# GAlarm-board.net
KiCad netlist of a schematic drawn in EAGLE
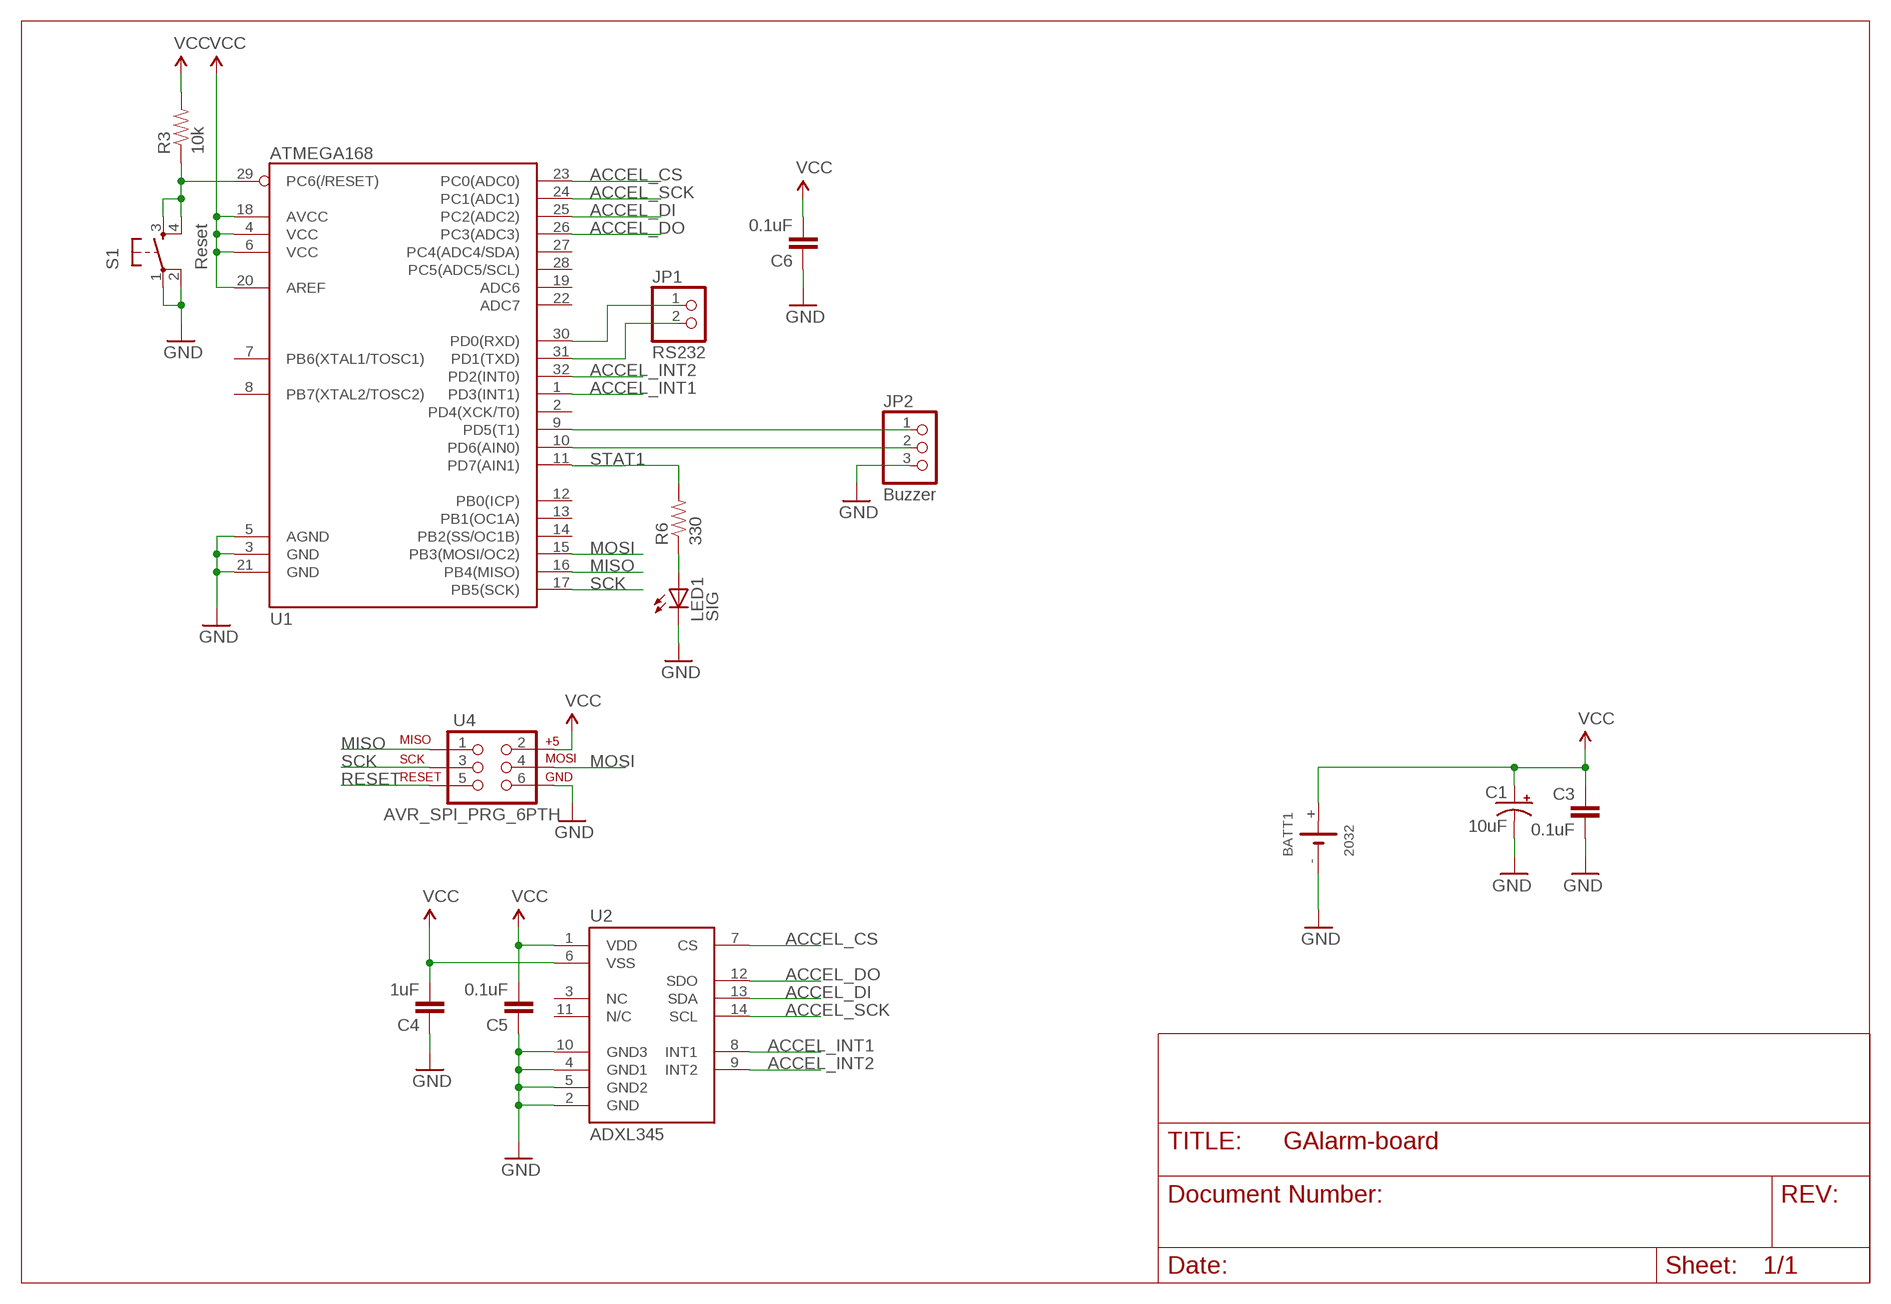
[diagram p0: schematic, sheet 1]

(export (version "E")
  (design (tool "Eeschema 10.0.6"))
  (components
    (comp (ref "BATT1")
      (value "2032")
      (footprint "eagle-import:2032_SMD")
      (libsource (lib "eagle-import") (part "CR2032_HOLDSMD"))
    )
    (comp (ref "C1")
      (value "10uF")
      (footprint "eagle-import:EIA3216")
      (libsource (lib "eagle-import") (part "CAP_POL1206"))
    )
    (comp (ref "C3")
      (value "0.1uF")
      (footprint "eagle-import:0603-CAP")
      (libsource (lib "eagle-import") (part "CAP0603-CAP"))
    )
    (comp (ref "C4")
      (value "1uF")
      (footprint "eagle-import:0805")
      (libsource (lib "eagle-import") (part "CAP0805"))
    )
    (comp (ref "C5")
      (value "0.1uF")
      (footprint "eagle-import:0603-CAP")
      (libsource (lib "eagle-import") (part "CAP0603-CAP"))
    )
    (comp (ref "C6")
      (value "0.1uF")
      (footprint "eagle-import:0603-CAP")
      (libsource (lib "eagle-import") (part "CAP0603-CAP"))
    )
    (comp (ref "JP1")
      (value "RS232")
      (footprint "eagle-import:1X02")
      (libsource (lib "eagle-import") (part "PINHD-1X2"))
    )
    (comp (ref "JP2")
      (value "Buzzer")
      (footprint "eagle-import:1X03")
      (libsource (lib "eagle-import") (part "PINHD-1X3"))
    )
    (comp (ref "LED1")
      (value "SIG")
      (footprint "eagle-import:LED-0603")
      (libsource (lib "eagle-import") (part "LED0603"))
    )
    (comp (ref "R3")
      (value "10k")
      (footprint "eagle-import:0603-RES")
      (libsource (lib "eagle-import") (part "RESISTOR0603-RES"))
    )
    (comp (ref "R6")
      (value "330")
      (footprint "eagle-import:0603-RES")
      (libsource (lib "eagle-import") (part "RESISTOR0603-RES"))
    )
    (comp (ref "S1")
      (value "Reset")
      (footprint "eagle-import:TACTILE_SWITCH_SMD")
      (libsource (lib "eagle-import") (part "TAC_SWITCHSMD"))
    )
    (comp (ref "U1")
      (value "ATMEGA168")
      (footprint "eagle-import:TQFP32-08")
      (libsource (lib "eagle-import") (part "ATMEGA168"))
    )
    (comp (ref "U2")
      (value "ADXL345")
      (footprint "eagle-import:LGA14")
      (libsource (lib "eagle-import") (part "ADXL345"))
    )
    (comp (ref "U4")
      (value "AVR_SPI_PRG_6PTH")
      (footprint "eagle-import:2X3")
      (libsource (lib "eagle-import") (part "AVR_SPI_PRG_6PTH"))
    )
  )
  (nets
    (net (code "1") (name "/ACCEL_CS") (class "Default")
      (node (ref "U1") (pin "23") (pinfunction "PC0(ADC0)_23") (pintype "bidirectional"))
      (node (ref "U2") (pin "7") (pinfunction "CS_7") (pintype "bidirectional"))
    )
    (net (code "2") (name "/ACCEL_DI") (class "Default")
      (node (ref "U1") (pin "25") (pinfunction "PC2(ADC2)_25") (pintype "bidirectional"))
      (node (ref "U2") (pin "13") (pinfunction "SDA_13") (pintype "bidirectional"))
    )
    (net (code "3") (name "/ACCEL_DO") (class "Default")
      (node (ref "U1") (pin "26") (pinfunction "PC3(ADC3)_26") (pintype "bidirectional"))
      (node (ref "U2") (pin "12") (pinfunction "SDO_12") (pintype "bidirectional"))
    )
    (net (code "4") (name "/ACCEL_INT1") (class "Default")
      (node (ref "U1") (pin "1") (pinfunction "PD3(INT1)_1") (pintype "bidirectional"))
      (node (ref "U2") (pin "8") (pinfunction "INT1_8") (pintype "bidirectional"))
    )
    (net (code "5") (name "/ACCEL_INT2") (class "Default")
      (node (ref "U1") (pin "32") (pinfunction "PD2(INT0)_32") (pintype "bidirectional"))
      (node (ref "U2") (pin "9") (pinfunction "INT2_9") (pintype "bidirectional"))
    )
    (net (code "6") (name "/ACCEL_SCK") (class "Default")
      (node (ref "U1") (pin "24") (pinfunction "PC1(ADC1)_24") (pintype "bidirectional"))
      (node (ref "U2") (pin "14") (pinfunction "SCL_14") (pintype "bidirectional"))
    )
    (net (code "7") (name "/MISO") (class "Default")
      (node (ref "U1") (pin "16") (pinfunction "PB4(MISO)_16") (pintype "bidirectional"))
      (node (ref "U4") (pin "1") (pinfunction "1_1") (pintype "passive"))
    )
    (net (code "8") (name "/MOSI") (class "Default")
      (node (ref "U1") (pin "15") (pinfunction "PB3(MOSI/OC2)_15") (pintype "bidirectional"))
      (node (ref "U4") (pin "4") (pinfunction "4_4") (pintype "passive"))
    )
    (net (code "9") (name "/RESET") (class "Default")
      (node (ref "R3") (pin "1") (pinfunction "1_1") (pintype "passive"))
      (node (ref "S1") (pin "3") (pinfunction "3_3") (pintype "passive"))
      (node (ref "S1") (pin "4") (pinfunction "4_4") (pintype "passive"))
      (node (ref "U1") (pin "29") (pinfunction "PC6(/RESET)_29") (pintype "bidirectional"))
      (node (ref "U4") (pin "5") (pinfunction "5_5") (pintype "passive"))
    )
    (net (code "10") (name "/SCK") (class "Default")
      (node (ref "U1") (pin "17") (pinfunction "PB5(SCK)_17") (pintype "bidirectional"))
      (node (ref "U4") (pin "3") (pinfunction "3_3") (pintype "passive"))
    )
    (net (code "11") (name "/STAT1") (class "Default")
      (node (ref "R6") (pin "2") (pinfunction "2_2") (pintype "passive"))
      (node (ref "U1") (pin "11") (pinfunction "PD7(AIN1)_11") (pintype "bidirectional"))
    )
    (net (code "12") (name "GND") (class "Default")
      (node (ref "BATT1") (pin "-") (pinfunction "-_-") (pintype "passive"))
      (node (ref "C1") (pin "C") (pinfunction "-_C") (pintype "passive"))
      (node (ref "C3") (pin "2") (pinfunction "2_2") (pintype "passive"))
      (node (ref "C4") (pin "1") (pinfunction "1_1") (pintype "passive"))
      (node (ref "C5") (pin "1") (pinfunction "1_1") (pintype "passive"))
      (node (ref "C6") (pin "1") (pinfunction "1_1") (pintype "passive"))
      (node (ref "JP2") (pin "3") (pinfunction "3_3") (pintype "passive"))
      (node (ref "LED1") (pin "C") (pinfunction "C_C") (pintype "passive"))
      (node (ref "S1") (pin "1") (pinfunction "1_1") (pintype "passive"))
      (node (ref "S1") (pin "2") (pinfunction "2_2") (pintype "passive"))
      (node (ref "U1") (pin "21") (pinfunction "GND_21") (pintype "bidirectional"))
      (node (ref "U1") (pin "3") (pinfunction "GND_3") (pintype "bidirectional"))
      (node (ref "U1") (pin "5") (pinfunction "AGND_5") (pintype "bidirectional"))
      (node (ref "U2") (pin "10") (pinfunction "GND3_10") (pintype "bidirectional"))
      (node (ref "U2") (pin "2") (pinfunction "GND_2") (pintype "bidirectional"))
      (node (ref "U2") (pin "4") (pinfunction "GND1_4") (pintype "bidirectional"))
      (node (ref "U2") (pin "5") (pinfunction "GND2_5") (pintype "bidirectional"))
      (node (ref "U4") (pin "6") (pinfunction "6_6") (pintype "passive"))
    )
    (net (code "13") (name "Net-(LED1-PadA)") (class "Default")
      (node (ref "LED1") (pin "A") (pinfunction "A_A") (pintype "passive"))
      (node (ref "R6") (pin "1") (pinfunction "1_1") (pintype "passive"))
    )
    (net (code "14") (name "Net-(U1-PD0(RXD))") (class "Default")
      (node (ref "JP1") (pin "1") (pinfunction "1_1") (pintype "passive"))
      (node (ref "U1") (pin "30") (pinfunction "PD0(RXD)_30") (pintype "bidirectional"))
    )
    (net (code "15") (name "Net-(U1-PD1(TXD))") (class "Default")
      (node (ref "JP1") (pin "2") (pinfunction "2_2") (pintype "passive"))
      (node (ref "U1") (pin "31") (pinfunction "PD1(TXD)_31") (pintype "bidirectional"))
    )
    (net (code "16") (name "Net-(U1-PD5(T1))") (class "Default")
      (node (ref "JP2") (pin "1") (pinfunction "1_1") (pintype "passive"))
      (node (ref "U1") (pin "9") (pinfunction "PD5(T1)_9") (pintype "bidirectional"))
    )
    (net (code "17") (name "Net-(U1-PD6(AIN0))") (class "Default")
      (node (ref "JP2") (pin "2") (pinfunction "2_2") (pintype "passive"))
      (node (ref "U1") (pin "10") (pinfunction "PD6(AIN0)_10") (pintype "bidirectional"))
    )
    (net (code "18") (name "VCC") (class "Default")
      (node (ref "BATT1") (pin "+") (pinfunction "+_+") (pintype "passive"))
      (node (ref "C1") (pin "A") (pinfunction "+_A") (pintype "passive"))
      (node (ref "C3") (pin "1") (pinfunction "1_1") (pintype "passive"))
      (node (ref "C4") (pin "2") (pinfunction "2_2") (pintype "passive"))
      (node (ref "C5") (pin "2") (pinfunction "2_2") (pintype "passive"))
      (node (ref "C6") (pin "2") (pinfunction "2_2") (pintype "passive"))
      (node (ref "R3") (pin "2") (pinfunction "2_2") (pintype "passive"))
      (node (ref "U1") (pin "18") (pinfunction "AVCC_18") (pintype "bidirectional"))
      (node (ref "U1") (pin "20") (pinfunction "AREF_20") (pintype "bidirectional"))
      (node (ref "U1") (pin "4") (pinfunction "VCC_4") (pintype "bidirectional"))
      (node (ref "U1") (pin "6") (pinfunction "VCC_6") (pintype "bidirectional"))
      (node (ref "U2") (pin "1") (pinfunction "VDD_1") (pintype "bidirectional"))
      (node (ref "U2") (pin "6") (pinfunction "VSS_6") (pintype "bidirectional"))
      (node (ref "U4") (pin "2") (pinfunction "2_2") (pintype "passive"))
    )
    (net (code "19") (name "unconnected-(U1-ADC6-Pad19)") (class "Default")
      (node (ref "U1") (pin "19") (pinfunction "ADC6_19") (pintype "bidirectional"))
    )
    (net (code "20") (name "unconnected-(U1-ADC7-Pad22)") (class "Default")
      (node (ref "U1") (pin "22") (pinfunction "ADC7_22") (pintype "bidirectional"))
    )
    (net (code "21") (name "unconnected-(U1-PB0(ICP)-Pad12)") (class "Default")
      (node (ref "U1") (pin "12") (pinfunction "PB0(ICP)_12") (pintype "bidirectional"))
    )
    (net (code "22") (name "unconnected-(U1-PB1(OC1A)-Pad13)") (class "Default")
      (node (ref "U1") (pin "13") (pinfunction "PB1(OC1A)_13") (pintype "bidirectional"))
    )
    (net (code "23") (name "unconnected-(U1-PB2(SS{slash}OC1B)-Pad14)") (class "Default")
      (node (ref "U1") (pin "14") (pinfunction "PB2(SS/OC1B)_14") (pintype "bidirectional"))
    )
    (net (code "24") (name "unconnected-(U1-PB6(XTAL1{slash}TOSC1)-Pad7)") (class "Default")
      (node (ref "U1") (pin "7") (pinfunction "PB6(XTAL1/TOSC1)_7") (pintype "bidirectional"))
    )
    (net (code "25") (name "unconnected-(U1-PB7(XTAL2{slash}TOSC2)-Pad8)") (class "Default")
      (node (ref "U1") (pin "8") (pinfunction "PB7(XTAL2/TOSC2)_8") (pintype "bidirectional"))
    )
    (net (code "26") (name "unconnected-(U1-PC4(ADC4{slash}SDA)-Pad27)") (class "Default")
      (node (ref "U1") (pin "27") (pinfunction "PC4(ADC4/SDA)_27") (pintype "bidirectional"))
    )
    (net (code "27") (name "unconnected-(U1-PC5(ADC5{slash}SCL)-Pad28)") (class "Default")
      (node (ref "U1") (pin "28") (pinfunction "PC5(ADC5/SCL)_28") (pintype "bidirectional"))
    )
    (net (code "28") (name "unconnected-(U1-PD4(XCK{slash}T0)-Pad2)") (class "Default")
      (node (ref "U1") (pin "2") (pinfunction "PD4(XCK/T0)_2") (pintype "bidirectional"))
    )
    (net (code "29") (name "unconnected-(U2-NC-Pad3)") (class "Default")
      (node (ref "U2") (pin "3") (pinfunction "NC_3") (pintype "bidirectional"))
    )
    (net (code "30") (name "unconnected-(U2-N{slash}C-Pad11)") (class "Default")
      (node (ref "U2") (pin "11") (pinfunction "N/C_11") (pintype "bidirectional"))
    )
  )
)
